# Z80HW.net
KiCad netlist of a schematic drawn in EAGLE
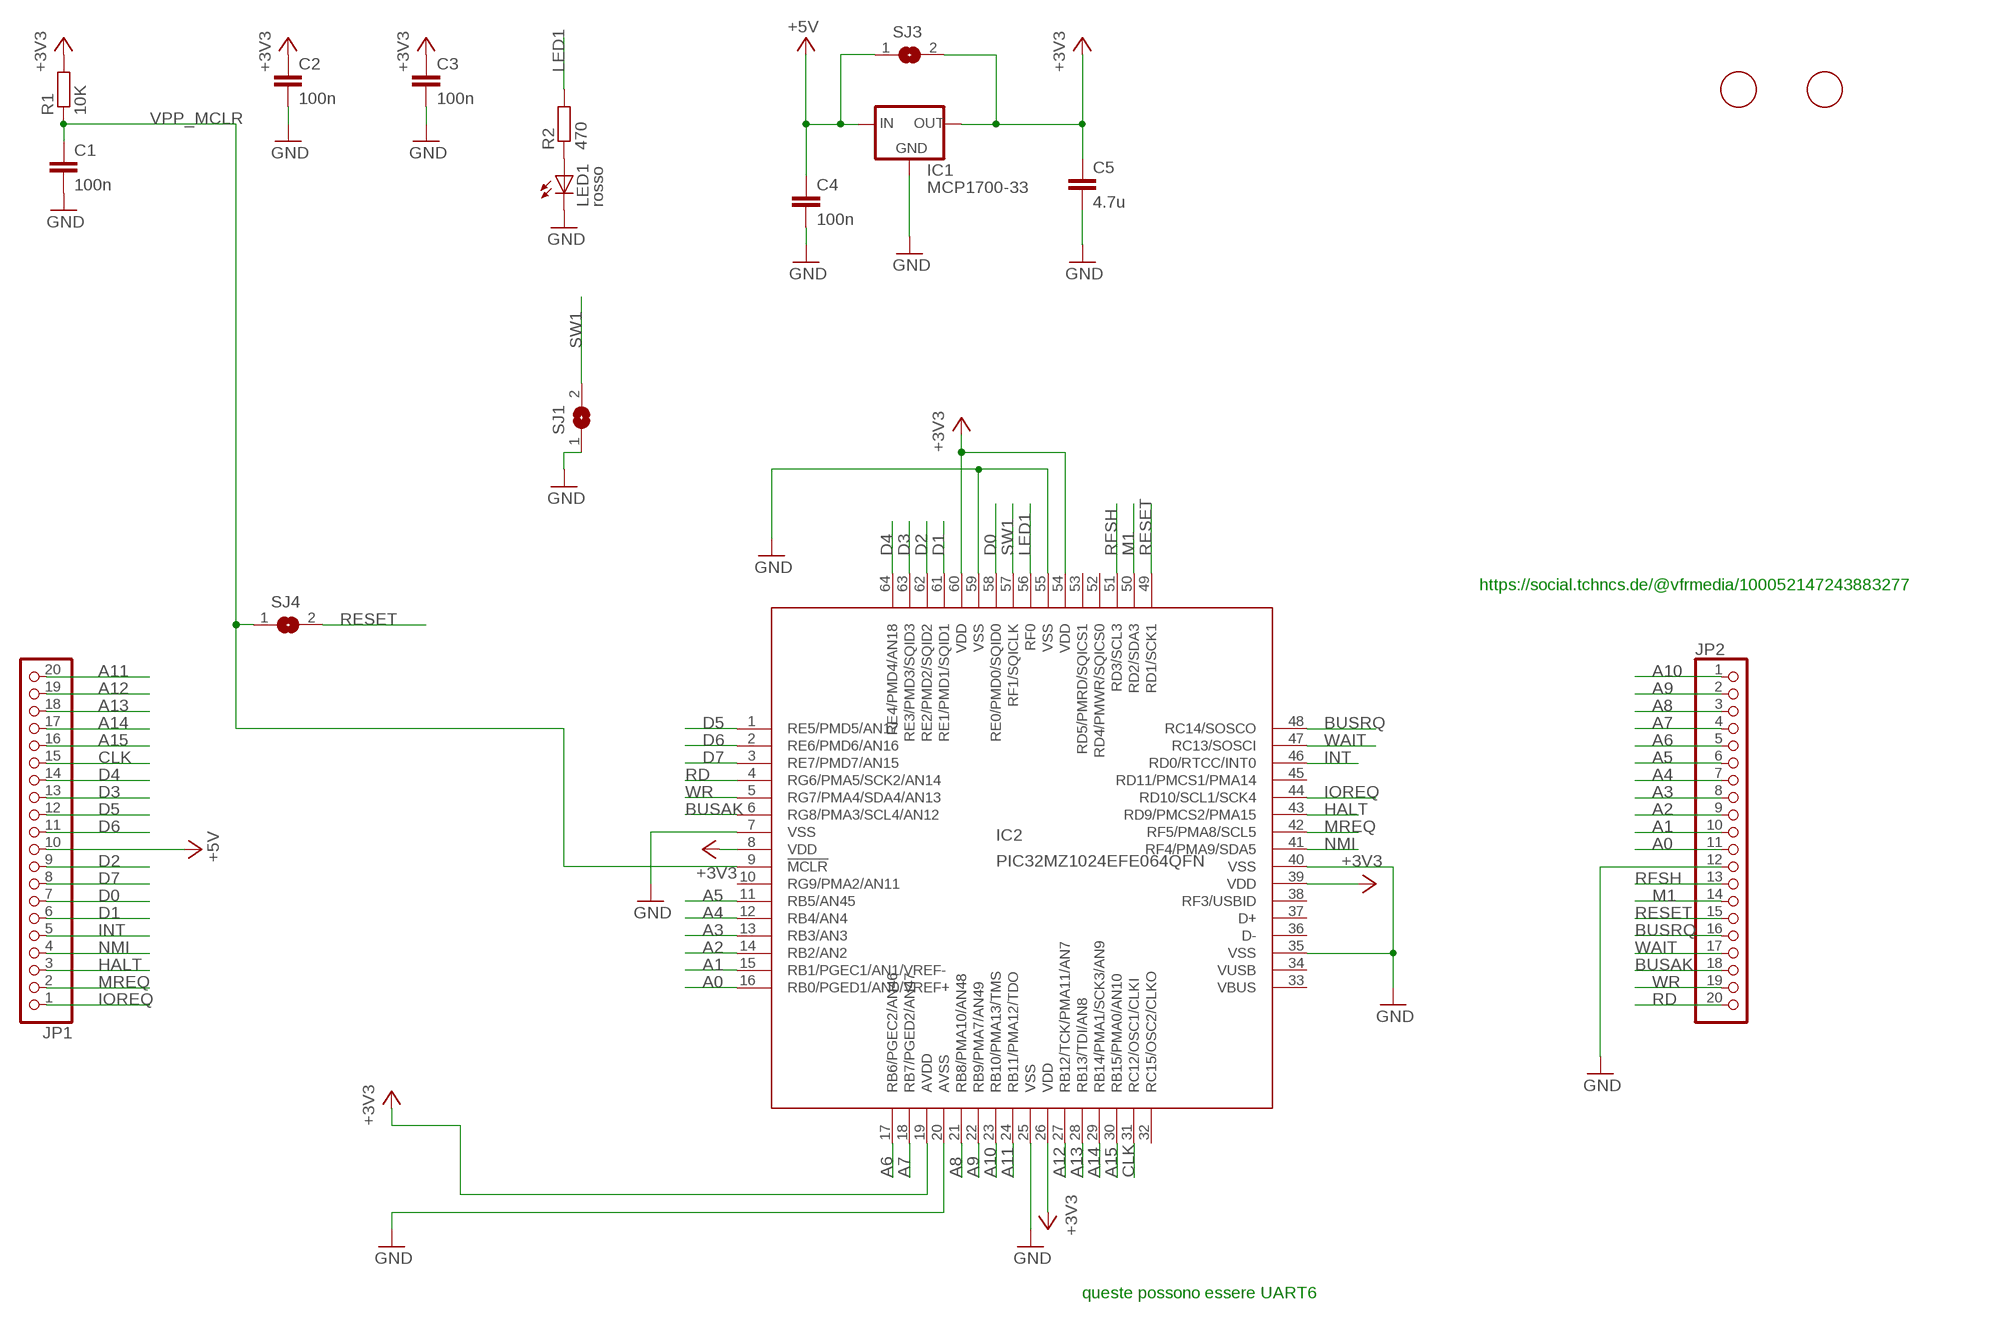
[diagram p0: schematic, sheet 1]

(export (version "E")
  (design (tool "Eeschema 10.0.6"))
  (components
    (comp (ref "C1")
      (value "100n")
      (footprint "eagle-import:C0805")
      (libsource (lib "eagle-import") (part "C-EUC0805"))
    )
    (comp (ref "C2")
      (value "100n")
      (footprint "eagle-import:C0805")
      (libsource (lib "eagle-import") (part "C-EUC0805"))
    )
    (comp (ref "C3")
      (value "100n")
      (footprint "eagle-import:C0805")
      (libsource (lib "eagle-import") (part "C-EUC0805"))
    )
    (comp (ref "C4")
      (value "100n")
      (footprint "eagle-import:C0805")
      (libsource (lib "eagle-import") (part "C-EUC0805"))
    )
    (comp (ref "C5")
      (value "4.7u")
      (footprint "eagle-import:C1206")
      (libsource (lib "eagle-import") (part "C-EUC1206"))
    )
    (comp (ref "F1")
      (value "FIDUCIAL")
      (footprint "eagle-import:FIDUCIAL_1MM")
      (libsource (lib "eagle-import") (part "FIDUCIAL"))
    )
    (comp (ref "F2")
      (value "FIDUCIAL")
      (footprint "eagle-import:FIDUCIAL_1MM")
      (libsource (lib "eagle-import") (part "FIDUCIAL"))
    )
    (comp (ref "IC1")
      (value "MCP1700-33")
      (footprint "eagle-import:SOT23")
      (libsource (lib "eagle-import") (part "MCP1700SOT23"))
    )
    (comp (ref "IC2")
      (value "PIC32MZ1024EFE064QFN")
      (footprint "eagle-import:QFN64")
      (libsource (lib "eagle-import") (part "PIC32MZ1024EFE064QFN"))
    )
    (comp (ref "JP1")
      (value "PINHD-1X20_2.54")
      (footprint "eagle-import:1X20")
      (libsource (lib "eagle-import") (part "PINHD-1X20_2.54"))
    )
    (comp (ref "JP2")
      (value "PINHD-1X20_2.54")
      (footprint "eagle-import:1X20")
      (libsource (lib "eagle-import") (part "PINHD-1X20_2.54"))
    )
    (comp (ref "LED1")
      (value "rosso")
      (footprint "eagle-import:CHIPLED_0805")
      (libsource (lib "eagle-import") (part "LEDCHIPLED_0805"))
    )
    (comp (ref "R1")
      (value "10K")
      (footprint "eagle-import:R0805")
      (libsource (lib "eagle-import") (part "R-EU_R0805"))
    )
    (comp (ref "R2")
      (value "470")
      (footprint "eagle-import:R0805")
      (libsource (lib "eagle-import") (part "R-EU_R0805"))
    )
    (comp (ref "SJ1") (value "SJ") (footprint "eagle-import:SJ") (libsource (lib "eagle-import") (part "SJ")))
    (comp (ref "SJ3") (value "SJ") (footprint "eagle-import:SJ") (libsource (lib "eagle-import") (part "SJ")))
    (comp (ref "SJ4") (value "SJ") (footprint "eagle-import:SJ") (libsource (lib "eagle-import") (part "SJ")))
  )
  (nets
    (net (code "1") (name "+3V3") (class "Default")
      (node (ref "C2") (pin "1") (pinfunction "1_1") (pintype "passive"))
      (node (ref "C3") (pin "1") (pinfunction "1_1") (pintype "passive"))
      (node (ref "C5") (pin "1") (pinfunction "1_1") (pintype "passive"))
      (node (ref "IC1") (pin "2") (pinfunction "OUT_2") (pintype "passive"))
      (node (ref "IC2") (pin "19") (pinfunction "AVDD_19") (pintype "power_in"))
      (node (ref "IC2") (pin "26") (pinfunction "VDD_26") (pintype "power_in"))
      (node (ref "IC2") (pin "39") (pinfunction "VDD_39") (pintype "power_in"))
      (node (ref "IC2") (pin "54") (pinfunction "VDD_54") (pintype "power_in"))
      (node (ref "IC2") (pin "60") (pinfunction "VDD_60") (pintype "power_in"))
      (node (ref "IC2") (pin "8") (pinfunction "VDD_8") (pintype "power_in"))
      (node (ref "R1") (pin "2") (pinfunction "2_2") (pintype "passive"))
      (node (ref "SJ3") (pin "2") (pinfunction "2_2") (pintype "passive"))
    )
    (net (code "2") (name "+5V") (class "Default")
      (node (ref "C4") (pin "1") (pinfunction "1_1") (pintype "passive"))
      (node (ref "IC1") (pin "3") (pinfunction "IN_3") (pintype "input"))
      (node (ref "JP1") (pin "10") (pinfunction "10_10") (pintype "passive"))
      (node (ref "SJ3") (pin "1") (pinfunction "1_1") (pintype "passive"))
    )
    (net (code "3") (name "/A0") (class "Default")
      (node (ref "IC2") (pin "16") (pinfunction "RB0/PGED1/AN0/VREF+_16") (pintype "bidirectional"))
      (node (ref "JP2") (pin "11") (pinfunction "11_11") (pintype "passive"))
    )
    (net (code "4") (name "/A1") (class "Default")
      (node (ref "IC2") (pin "15") (pinfunction "RB1/PGEC1/AN1/VREF-_15") (pintype "bidirectional"))
      (node (ref "JP2") (pin "10") (pinfunction "10_10") (pintype "passive"))
    )
    (net (code "5") (name "/A2") (class "Default")
      (node (ref "IC2") (pin "14") (pinfunction "RB2/AN2_14") (pintype "bidirectional"))
      (node (ref "JP2") (pin "9") (pinfunction "9_9") (pintype "passive"))
    )
    (net (code "6") (name "/A3") (class "Default")
      (node (ref "IC2") (pin "13") (pinfunction "RB3/AN3_13") (pintype "bidirectional"))
      (node (ref "JP2") (pin "8") (pinfunction "8_8") (pintype "passive"))
    )
    (net (code "7") (name "/A4") (class "Default")
      (node (ref "IC2") (pin "12") (pinfunction "RB4/AN4_12") (pintype "bidirectional"))
      (node (ref "JP2") (pin "7") (pinfunction "7_7") (pintype "passive"))
    )
    (net (code "8") (name "/A5") (class "Default")
      (node (ref "IC2") (pin "11") (pinfunction "RB5/AN45_11") (pintype "bidirectional"))
      (node (ref "JP2") (pin "6") (pinfunction "6_6") (pintype "passive"))
    )
    (net (code "9") (name "/A6") (class "Default")
      (node (ref "IC2") (pin "17") (pinfunction "RB6/PGEC2/AN46_17") (pintype "bidirectional"))
      (node (ref "JP2") (pin "5") (pinfunction "5_5") (pintype "passive"))
    )
    (net (code "10") (name "/A7") (class "Default")
      (node (ref "IC2") (pin "18") (pinfunction "RB7/PGED2/AN47_18") (pintype "bidirectional"))
      (node (ref "JP2") (pin "4") (pinfunction "4_4") (pintype "passive"))
    )
    (net (code "11") (name "/A8") (class "Default")
      (node (ref "IC2") (pin "21") (pinfunction "RB8/PMA10/AN48_21") (pintype "bidirectional"))
      (node (ref "JP2") (pin "3") (pinfunction "3_3") (pintype "passive"))
    )
    (net (code "12") (name "/A9") (class "Default")
      (node (ref "IC2") (pin "22") (pinfunction "RB9/PMA7/AN49_22") (pintype "bidirectional"))
      (node (ref "JP2") (pin "2") (pinfunction "2_2") (pintype "passive"))
    )
    (net (code "13") (name "/A10") (class "Default")
      (node (ref "IC2") (pin "23") (pinfunction "RB10/PMA13/TMS_23") (pintype "bidirectional"))
      (node (ref "JP2") (pin "1") (pinfunction "1_1") (pintype "passive"))
    )
    (net (code "14") (name "/A11") (class "Default")
      (node (ref "IC2") (pin "24") (pinfunction "RB11/PMA12/TDO_24") (pintype "bidirectional"))
      (node (ref "JP1") (pin "20") (pinfunction "20_20") (pintype "passive"))
    )
    (net (code "15") (name "/A12") (class "Default")
      (node (ref "IC2") (pin "27") (pinfunction "RB12/TCK/PMA11/AN7_27") (pintype "bidirectional"))
      (node (ref "JP1") (pin "19") (pinfunction "19_19") (pintype "passive"))
    )
    (net (code "16") (name "/A13") (class "Default")
      (node (ref "IC2") (pin "28") (pinfunction "RB13/TDI/AN8_28") (pintype "bidirectional"))
      (node (ref "JP1") (pin "18") (pinfunction "18_18") (pintype "passive"))
    )
    (net (code "17") (name "/A14") (class "Default")
      (node (ref "IC2") (pin "29") (pinfunction "RB14/PMA1/SCK3/AN9_29") (pintype "bidirectional"))
      (node (ref "JP1") (pin "17") (pinfunction "17_17") (pintype "passive"))
    )
    (net (code "18") (name "/A15") (class "Default")
      (node (ref "IC2") (pin "30") (pinfunction "RB15/PMA0/AN10_30") (pintype "bidirectional"))
      (node (ref "JP1") (pin "16") (pinfunction "16_16") (pintype "passive"))
    )
    (net (code "19") (name "/BUSAK") (class "Default")
      (node (ref "IC2") (pin "6") (pinfunction "RG8/PMA3/SCL4/AN12_6") (pintype "bidirectional"))
      (node (ref "JP2") (pin "18") (pinfunction "18_18") (pintype "passive"))
    )
    (net (code "20") (name "/BUSRQ") (class "Default")
      (node (ref "IC2") (pin "48") (pinfunction "RC14/SOSCO_48") (pintype "bidirectional"))
      (node (ref "JP2") (pin "16") (pinfunction "16_16") (pintype "passive"))
    )
    (net (code "21") (name "/CLK") (class "Default")
      (node (ref "IC2") (pin "31") (pinfunction "RC12/OSC1/CLKI_31") (pintype "bidirectional"))
      (node (ref "JP1") (pin "15") (pinfunction "15_15") (pintype "passive"))
    )
    (net (code "22") (name "/D0") (class "Default")
      (node (ref "IC2") (pin "58") (pinfunction "RE0/PMD0/SQID0_58") (pintype "bidirectional"))
      (node (ref "JP1") (pin "7") (pinfunction "7_7") (pintype "passive"))
    )
    (net (code "23") (name "/D1") (class "Default")
      (node (ref "IC2") (pin "61") (pinfunction "RE1/PMD1/SQID1_61") (pintype "bidirectional"))
      (node (ref "JP1") (pin "6") (pinfunction "6_6") (pintype "passive"))
    )
    (net (code "24") (name "/D2") (class "Default")
      (node (ref "IC2") (pin "62") (pinfunction "RE2/PMD2/SQID2_62") (pintype "bidirectional"))
      (node (ref "JP1") (pin "9") (pinfunction "9_9") (pintype "passive"))
    )
    (net (code "25") (name "/D3") (class "Default")
      (node (ref "IC2") (pin "63") (pinfunction "RE3/PMD3/SQID3_63") (pintype "bidirectional"))
      (node (ref "JP1") (pin "13") (pinfunction "13_13") (pintype "passive"))
    )
    (net (code "26") (name "/D4") (class "Default")
      (node (ref "IC2") (pin "64") (pinfunction "RE4/PMD4/AN18_64") (pintype "bidirectional"))
      (node (ref "JP1") (pin "14") (pinfunction "14_14") (pintype "passive"))
    )
    (net (code "27") (name "/D5") (class "Default")
      (node (ref "IC2") (pin "1") (pinfunction "RE5/PMD5/AN17_1") (pintype "bidirectional"))
      (node (ref "JP1") (pin "12") (pinfunction "12_12") (pintype "passive"))
    )
    (net (code "28") (name "/D6") (class "Default")
      (node (ref "IC2") (pin "2") (pinfunction "RE6/PMD6/AN16_2") (pintype "bidirectional"))
      (node (ref "JP1") (pin "11") (pinfunction "11_11") (pintype "passive"))
    )
    (net (code "29") (name "/D7") (class "Default")
      (node (ref "IC2") (pin "3") (pinfunction "RE7/PMD7/AN15_3") (pintype "bidirectional"))
      (node (ref "JP1") (pin "8") (pinfunction "8_8") (pintype "passive"))
    )
    (net (code "30") (name "/HALT") (class "Default")
      (node (ref "IC2") (pin "43") (pinfunction "RD9/PMCS2/PMA15_43") (pintype "bidirectional"))
      (node (ref "JP1") (pin "3") (pinfunction "3_3") (pintype "passive"))
    )
    (net (code "31") (name "/INT") (class "Default")
      (node (ref "IC2") (pin "46") (pinfunction "RD0/RTCC/INT0_46") (pintype "bidirectional"))
      (node (ref "JP1") (pin "5") (pinfunction "5_5") (pintype "passive"))
    )
    (net (code "32") (name "/IOREQ") (class "Default")
      (node (ref "IC2") (pin "44") (pinfunction "RD10/SCL1/SCK4_44") (pintype "bidirectional"))
      (node (ref "JP1") (pin "1") (pinfunction "1_1") (pintype "passive"))
    )
    (net (code "33") (name "/LED1") (class "Default")
      (node (ref "IC2") (pin "56") (pinfunction "RF0_56") (pintype "bidirectional"))
      (node (ref "R2") (pin "2") (pinfunction "2_2") (pintype "passive"))
    )
    (net (code "34") (name "/M1") (class "Default")
      (node (ref "IC2") (pin "50") (pinfunction "RD2/SDA3_50") (pintype "bidirectional"))
      (node (ref "JP2") (pin "14") (pinfunction "14_14") (pintype "passive"))
    )
    (net (code "35") (name "/MREQ") (class "Default")
      (node (ref "IC2") (pin "42") (pinfunction "RF5/PMA8/SCL5_42") (pintype "bidirectional"))
      (node (ref "JP1") (pin "2") (pinfunction "2_2") (pintype "passive"))
    )
    (net (code "36") (name "/NMI") (class "Default")
      (node (ref "IC2") (pin "41") (pinfunction "RF4/PMA9/SDA5_41") (pintype "bidirectional"))
      (node (ref "JP1") (pin "4") (pinfunction "4_4") (pintype "passive"))
    )
    (net (code "37") (name "/RD") (class "Default")
      (node (ref "IC2") (pin "4") (pinfunction "RG6/PMA5/SCK2/AN14_4") (pintype "bidirectional"))
      (node (ref "JP2") (pin "20") (pinfunction "20_20") (pintype "passive"))
    )
    (net (code "38") (name "/RESET") (class "Default")
      (node (ref "IC2") (pin "49") (pinfunction "RD1/SCK1_49") (pintype "bidirectional"))
      (node (ref "JP2") (pin "15") (pinfunction "15_15") (pintype "passive"))
      (node (ref "SJ4") (pin "2") (pinfunction "2_2") (pintype "passive"))
    )
    (net (code "39") (name "/RFSH") (class "Default")
      (node (ref "IC2") (pin "51") (pinfunction "RD3/SCL3_51") (pintype "bidirectional"))
      (node (ref "JP2") (pin "13") (pinfunction "13_13") (pintype "passive"))
    )
    (net (code "40") (name "/SW1") (class "Default")
      (node (ref "IC2") (pin "57") (pinfunction "RF1/SQICLK_57") (pintype "bidirectional"))
      (node (ref "SJ1") (pin "2") (pinfunction "2_2") (pintype "passive"))
    )
    (net (code "41") (name "/VPP_MCLR") (class "Default")
      (node (ref "C1") (pin "1") (pinfunction "1_1") (pintype "passive"))
      (node (ref "IC2") (pin "9") (pinfunction "~{MCLR}_9") (pintype "input"))
      (node (ref "R1") (pin "1") (pinfunction "1_1") (pintype "passive"))
      (node (ref "SJ4") (pin "1") (pinfunction "1_1") (pintype "passive"))
    )
    (net (code "42") (name "/VUSB") (class "Default")
      (node (ref "IC2") (pin "34") (pinfunction "VUSB_34") (pintype "power_in"))
    )
    (net (code "43") (name "/WAIT") (class "Default")
      (node (ref "IC2") (pin "47") (pinfunction "RC13/SOSCI_47") (pintype "bidirectional"))
      (node (ref "JP2") (pin "17") (pinfunction "17_17") (pintype "passive"))
    )
    (net (code "44") (name "/WR") (class "Default")
      (node (ref "IC2") (pin "5") (pinfunction "RG7/PMA4/SDA4/AN13_5") (pintype "bidirectional"))
      (node (ref "JP2") (pin "19") (pinfunction "19_19") (pintype "passive"))
    )
    (net (code "45") (name "GND") (class "Default")
      (node (ref "C1") (pin "2") (pinfunction "2_2") (pintype "passive"))
      (node (ref "C2") (pin "2") (pinfunction "2_2") (pintype "passive"))
      (node (ref "C3") (pin "2") (pinfunction "2_2") (pintype "passive"))
      (node (ref "C4") (pin "2") (pinfunction "2_2") (pintype "passive"))
      (node (ref "C5") (pin "2") (pinfunction "2_2") (pintype "passive"))
      (node (ref "IC1") (pin "1") (pinfunction "GND_1") (pintype "input"))
      (node (ref "IC2") (pin "20") (pinfunction "AVSS_20") (pintype "power_in"))
      (node (ref "IC2") (pin "25") (pinfunction "VSS_25") (pintype "power_in"))
      (node (ref "IC2") (pin "35") (pinfunction "VSS_35") (pintype "power_in"))
      (node (ref "IC2") (pin "40") (pinfunction "VSS_40") (pintype "power_in"))
      (node (ref "IC2") (pin "55") (pinfunction "VSS_55") (pintype "power_in"))
      (node (ref "IC2") (pin "59") (pinfunction "VSS_59") (pintype "power_in"))
      (node (ref "IC2") (pin "7") (pinfunction "VSS_7") (pintype "power_in"))
      (node (ref "JP2") (pin "12") (pinfunction "12_12") (pintype "passive"))
      (node (ref "LED1") (pin "C") (pinfunction "C_C") (pintype "passive"))
      (node (ref "SJ1") (pin "1") (pinfunction "1_1") (pintype "passive"))
    )
    (net (code "46") (name "Net-(LED1-PadA)") (class "Default")
      (node (ref "LED1") (pin "A") (pinfunction "A_A") (pintype "passive"))
      (node (ref "R2") (pin "1") (pinfunction "1_1") (pintype "passive"))
    )
    (net (code "47") (name "unconnected-(IC2-D+-Pad37)") (class "Default")
      (node (ref "IC2") (pin "37") (pinfunction "D+_37") (pintype "passive"))
    )
    (net (code "48") (name "unconnected-(IC2-D--Pad36)") (class "Default")
      (node (ref "IC2") (pin "36") (pinfunction "D-_36") (pintype "passive"))
    )
    (net (code "49") (name "unconnected-(IC2-RC15{slash}OSC2{slash}CLKO-Pad32)") (class "Default")
      (node (ref "IC2") (pin "32") (pinfunction "RC15/OSC2/CLKO_32") (pintype "bidirectional"))
    )
    (net (code "50") (name "unconnected-(IC2-RD4{slash}PMWR{slash}SQICS0-Pad52)") (class "Default")
      (node (ref "IC2") (pin "52") (pinfunction "RD4/PMWR/SQICS0_52") (pintype "bidirectional"))
    )
    (net (code "51") (name "unconnected-(IC2-RD5{slash}PMRD{slash}SQICS1-Pad53)") (class "Default")
      (node (ref "IC2") (pin "53") (pinfunction "RD5/PMRD/SQICS1_53") (pintype "bidirectional"))
    )
    (net (code "52") (name "unconnected-(IC2-RD11{slash}PMCS1{slash}PMA14-Pad45)") (class "Default")
      (node (ref "IC2") (pin "45") (pinfunction "RD11/PMCS1/PMA14_45") (pintype "bidirectional"))
    )
    (net (code "53") (name "unconnected-(IC2-RF3{slash}USBID-Pad38)") (class "Default")
      (node (ref "IC2") (pin "38") (pinfunction "RF3/USBID_38") (pintype "bidirectional"))
    )
    (net (code "54") (name "unconnected-(IC2-RG9{slash}PMA2{slash}AN11-Pad10)") (class "Default")
      (node (ref "IC2") (pin "10") (pinfunction "RG9/PMA2/AN11_10") (pintype "bidirectional"))
    )
    (net (code "55") (name "unconnected-(IC2-VBUS-Pad33)") (class "Default")
      (node (ref "IC2") (pin "33") (pinfunction "VBUS_33") (pintype "passive"))
    )
  )
)
